# LEDHeart.net
KiCad netlist of a schematic drawn in Altium Designer
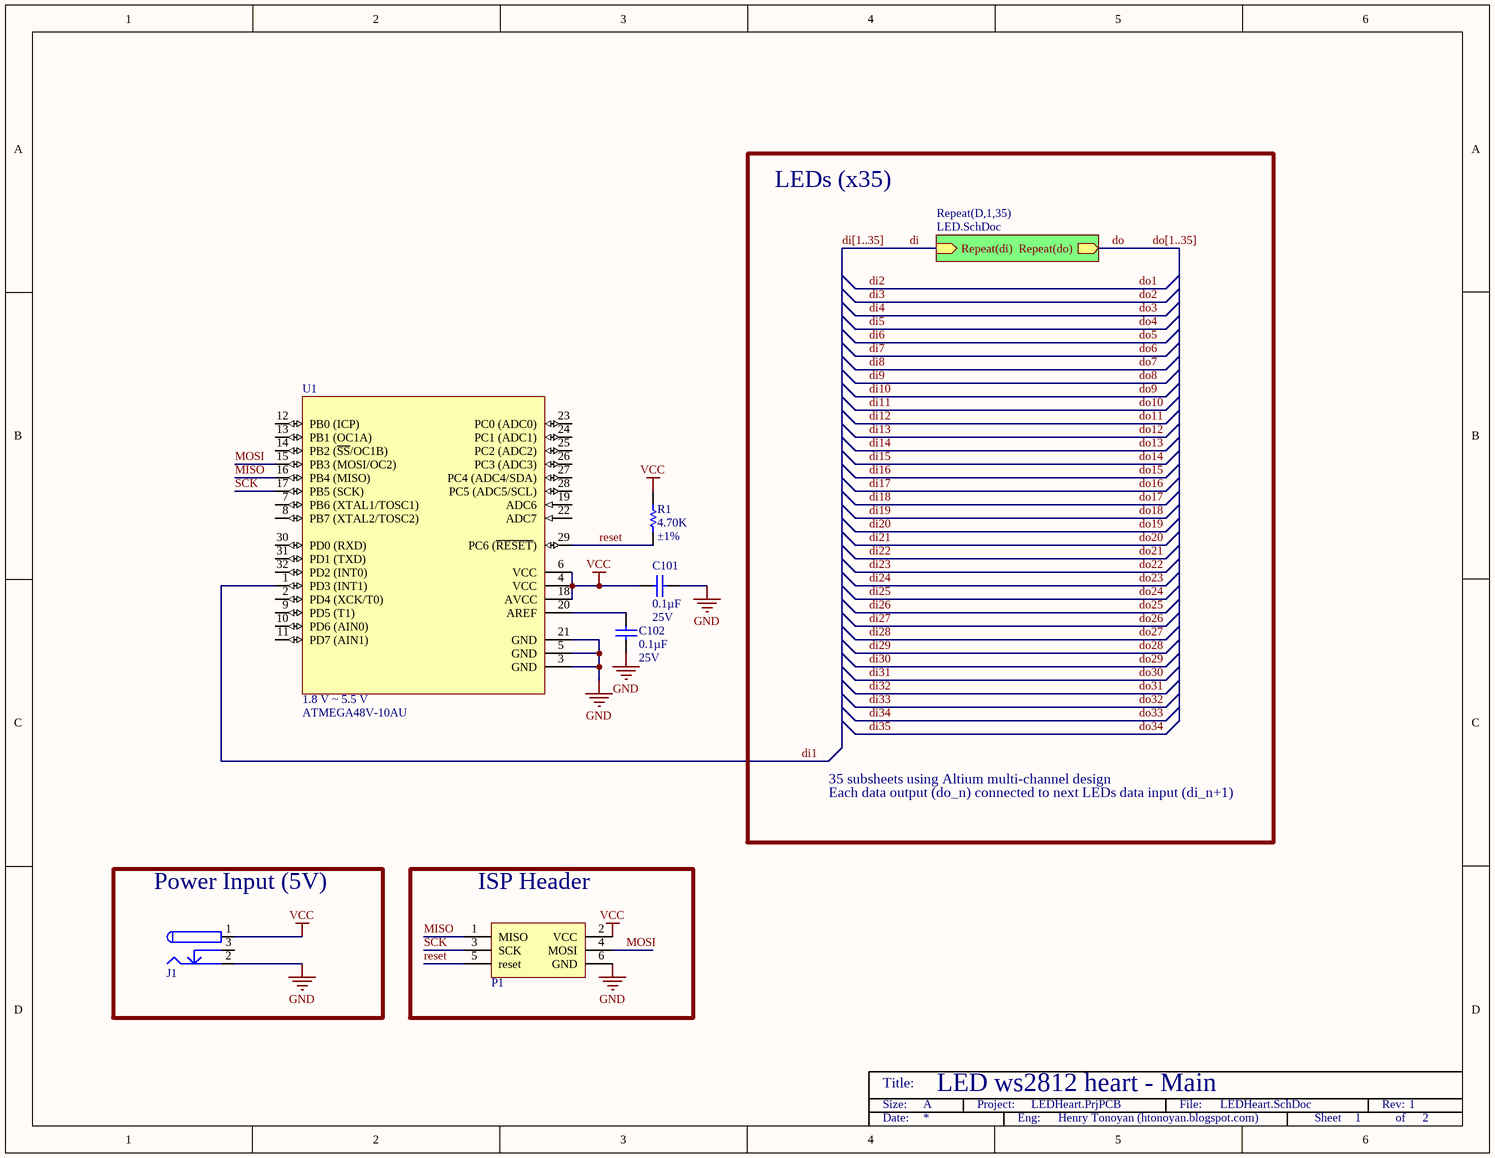
[diagram p0: LEDHeart.SchDoc]

(export (version "E")
  (design (tool "Eeschema 10.0.6"))
  (components
    (comp (ref "C101")
      (value "CAP CER .10UF 25V X7R 10% 0603")
      (footprint "0603")
      (fields
        (field (name "MANUFACTURER") "TDK Corporation")
        (field (name "MANUFACTURER PART NUMBER") "C1608X7R1E104K")
        (field (name "TOLERANCE") "±10%")
        (field (name "CAPACITANCE") "0.1µF")
        (field (name "VOLTAGE - RATED") "25V")
      )
      (libsource (lib "parts") (part "CAP_CER_.10UF_25V_X7R_10%_0603_1"))
    )
    (comp (ref "C102")
      (value "CAP CER .10UF 25V X7R 10% 0603")
      (footprint "0603")
      (fields
        (field (name "MANUFACTURER") "TDK Corporation")
        (field (name "MANUFACTURER PART NUMBER") "C1608X7R1E104K")
        (field (name "TOLERANCE") "±10%")
        (field (name "CAPACITANCE") "0.1µF")
        (field (name "VOLTAGE - RATED") "25V")
      )
      (libsource (lib "parts") (part "CAP_CER_.10UF_25V_X7R_10%_0603_1"))
    )
    (comp (ref "J1")
      (value "CONN_PWR2.0_SMT")
      (footprint "CONN_PWR2.0_SMT")
      (description "CONN PWR JACK 2.0X6.3MM SMT")
      (fields (field (name "MANUFACTURER") "CUI Inc") (field (name "MANUFACTURER PART NUMBER") "PJ-036A-SMT"))
      (libsource (lib "parts") (part "CONN_PWR2.0_SMT"))
    )
    (comp (ref "P1")
      (value "Header, 3-Pin, Dual row")
      (footprint "CONN_HDR_SMT_6_2R")
      (fields
        (field (name "MANUFACTURER") "Molex Connector Corporation")
        (field (name "MANUFACTURER PART NUMBER") "15-91-2060")
      )
      (libsource (lib "parts") (part "CONN_Header_0.100_6pos"))
    )
    (comp (ref "R1")
      (value "RES_4.70K_OHM_1/10W_1%_0603_SMD")
      (footprint "0603")
      (description "RES 4.70K OHM 1/10W 1% 0603 SMD")
      (fields
        (field (name "MANUFACTURER") "Panasonic Electronic Components")
        (field (name "MANUFACTURER PART NUMBER") "ERJ-3EKF4701V")
        (field (name "RESISTANCE (OHMS)") "4.70K")
        (field (name "TOLERANCE") "±1%")
      )
      (libsource (lib "parts") (part "RES_4.70K_OHM_1/10W_1%_0603_SMD"))
    )
    (comp (ref "U1")
      (value "IC_AVR_MCU_4K_10MHZ_1.8V_32TQFP")
      (footprint "32A_N")
      (description "IC AVR MCU 4K 10MHZ 1.8V 32TQFP")
      (fields
        (field (name "MANUFACTURER") "Atmel")
        (field (name "VOLTAGE - SUPPLY (VCC/VDD)") "1.8 V ~ 5.5 V")
        (field (name "MANUFACTURER PART NUMBER") "ATMEGA48V-10AU")
      )
      (libsource (lib "parts") (part "IC_AVR_MCU_4K_10MHZ_1.8V_32TQFP_1"))
    )
  )
  (nets
    (net (code "2") (name "/MISO") (class "Default")
      (node (ref "P1") (pin "1") (pinfunction "MISO_1") (pintype "passive"))
      (node (ref "U1") (pin "16") (pinfunction "PB4_(MISO)_16") (pintype "bidirectional"))
    )
    (net (code "3") (name "/MOSI") (class "Default")
      (node (ref "P1") (pin "4") (pinfunction "MOSI_4") (pintype "passive"))
      (node (ref "U1") (pin "15") (pinfunction "PB3_(MOSI/OC2)_15") (pintype "bidirectional"))
    )
    (net (code "4") (name "/SCK") (class "Default")
      (node (ref "P1") (pin "3") (pinfunction "SCK_3") (pintype "passive"))
      (node (ref "U1") (pin "17") (pinfunction "PB5_(SCK)_17") (pintype "bidirectional"))
    )
    (net (code "6") (name "/di1") (class "Default")
      (node (ref "U1") (pin "1") (pinfunction "PD3_(INT1)_1") (pintype "bidirectional"))
    )
    (net (code "44") (name "/reset") (class "Default")
      (node (ref "P1") (pin "5") (pinfunction "reset_5") (pintype "passive"))
      (node (ref "R1") (pin "1") (pinfunction "1_1") (pintype "passive"))
      (node (ref "U1") (pin "29") (pinfunction "PC6_(~{RESET})_29") (pintype "bidirectional"))
    )
    (net (code "45") (name "GND") (class "Default")
      (node (ref "C101") (pin "1") (pinfunction "1_1") (pintype "passive"))
      (node (ref "C102") (pin "1") (pinfunction "1_1") (pintype "passive"))
      (node (ref "J1") (pin "2") (pinfunction "2_2") (pintype "power_in"))
      (node (ref "P1") (pin "6") (pinfunction "GND_6") (pintype "passive"))
      (node (ref "U1") (pin "21") (pinfunction "GND_21") (pintype "power_in"))
      (node (ref "U1") (pin "3") (pinfunction "GND_3") (pintype "power_in"))
      (node (ref "U1") (pin "5") (pinfunction "GND_5") (pintype "power_in"))
    )
    (net (code "46") (name "Net-(U1-AREF)") (class "Default")
      (node (ref "C102") (pin "2") (pinfunction "2_2") (pintype "passive"))
      (node (ref "U1") (pin "20") (pinfunction "AREF_20") (pintype "passive"))
    )
    (net (code "47") (name "VCC") (class "Default")
      (node (ref "C101") (pin "2") (pinfunction "2_2") (pintype "passive"))
      (node (ref "J1") (pin "1") (pinfunction "1_1") (pintype "power_in"))
      (node (ref "P1") (pin "2") (pinfunction "VCC_2") (pintype "passive"))
      (node (ref "R1") (pin "2") (pinfunction "2_2") (pintype "passive"))
      (node (ref "U1") (pin "18") (pinfunction "AVCC_18") (pintype "power_in"))
      (node (ref "U1") (pin "4") (pinfunction "VCC_4") (pintype "power_in"))
      (node (ref "U1") (pin "6") (pinfunction "VCC_6") (pintype "power_in"))
    )
    (net (code "48") (name "unconnected-(J1-Pad3)") (class "Default")
      (node (ref "J1") (pin "3") (pinfunction "3_3") (pintype "power_in"))
    )
    (net (code "49") (name "unconnected-(U1-ADC6-Pad19)") (class "Default")
      (node (ref "U1") (pin "19") (pinfunction "ADC6_19") (pintype "input"))
    )
    (net (code "50") (name "unconnected-(U1-ADC7-Pad22)") (class "Default")
      (node (ref "U1") (pin "22") (pinfunction "ADC7_22") (pintype "input"))
    )
    (net (code "51") (name "unconnected-(U1-PB0_(ICP)-Pad12)") (class "Default")
      (node (ref "U1") (pin "12") (pinfunction "PB0_(ICP)_12") (pintype "bidirectional"))
    )
    (net (code "52") (name "unconnected-(U1-PB1_(OC1A)-Pad13)") (class "Default")
      (node (ref "U1") (pin "13") (pinfunction "PB1_(OC1A)_13") (pintype "bidirectional"))
    )
    (net (code "53") (name "unconnected-(U1-PB2_(~{SS}{slash}OC1B)-Pad14)") (class "Default")
      (node (ref "U1") (pin "14") (pinfunction "PB2_(~{SS}/OC1B)_14") (pintype "bidirectional"))
    )
    (net (code "54") (name "unconnected-(U1-PB6_(XTAL1{slash}TOSC1)-Pad7)") (class "Default")
      (node (ref "U1") (pin "7") (pinfunction "PB6_(XTAL1/TOSC1)_7") (pintype "bidirectional"))
    )
    (net (code "55") (name "unconnected-(U1-PB7_(XTAL2{slash}TOSC2)-Pad8)") (class "Default")
      (node (ref "U1") (pin "8") (pinfunction "PB7_(XTAL2/TOSC2)_8") (pintype "bidirectional"))
    )
    (net (code "56") (name "unconnected-(U1-PC0_(ADC0)-Pad23)") (class "Default")
      (node (ref "U1") (pin "23") (pinfunction "PC0_(ADC0)_23") (pintype "bidirectional"))
    )
    (net (code "57") (name "unconnected-(U1-PC1_(ADC1)-Pad24)") (class "Default")
      (node (ref "U1") (pin "24") (pinfunction "PC1_(ADC1)_24") (pintype "bidirectional"))
    )
    (net (code "58") (name "unconnected-(U1-PC2_(ADC2)-Pad25)") (class "Default")
      (node (ref "U1") (pin "25") (pinfunction "PC2_(ADC2)_25") (pintype "bidirectional"))
    )
    (net (code "59") (name "unconnected-(U1-PC3_(ADC3)-Pad26)") (class "Default")
      (node (ref "U1") (pin "26") (pinfunction "PC3_(ADC3)_26") (pintype "bidirectional"))
    )
    (net (code "60") (name "unconnected-(U1-PC4_(ADC4{slash}SDA)-Pad27)") (class "Default")
      (node (ref "U1") (pin "27") (pinfunction "PC4_(ADC4/SDA)_27") (pintype "bidirectional"))
    )
    (net (code "61") (name "unconnected-(U1-PC5_(ADC5{slash}SCL)-Pad28)") (class "Default")
      (node (ref "U1") (pin "28") (pinfunction "PC5_(ADC5/SCL)_28") (pintype "bidirectional"))
    )
    (net (code "62") (name "unconnected-(U1-PD0_(RXD)-Pad30)") (class "Default")
      (node (ref "U1") (pin "30") (pinfunction "PD0_(RXD)_30") (pintype "bidirectional"))
    )
    (net (code "63") (name "unconnected-(U1-PD1_(TXD)-Pad31)") (class "Default")
      (node (ref "U1") (pin "31") (pinfunction "PD1_(TXD)_31") (pintype "bidirectional"))
    )
    (net (code "64") (name "unconnected-(U1-PD2_(INT0)-Pad32)") (class "Default")
      (node (ref "U1") (pin "32") (pinfunction "PD2_(INT0)_32") (pintype "bidirectional"))
    )
    (net (code "65") (name "unconnected-(U1-PD4_(XCK{slash}T0)-Pad2)") (class "Default")
      (node (ref "U1") (pin "2") (pinfunction "PD4_(XCK/T0)_2") (pintype "bidirectional"))
    )
    (net (code "66") (name "unconnected-(U1-PD5_(T1)-Pad9)") (class "Default")
      (node (ref "U1") (pin "9") (pinfunction "PD5_(T1)_9") (pintype "bidirectional"))
    )
    (net (code "67") (name "unconnected-(U1-PD6_(AIN0)-Pad10)") (class "Default")
      (node (ref "U1") (pin "10") (pinfunction "PD6_(AIN0)_10") (pintype "bidirectional"))
    )
    (net (code "68") (name "unconnected-(U1-PD7_(AIN1)-Pad11)") (class "Default")
      (node (ref "U1") (pin "11") (pinfunction "PD7_(AIN1)_11") (pintype "bidirectional"))
    )
  )
)
